# P1-Port-Reader.net
KiCad netlist of a schematic drawn in EAGLE
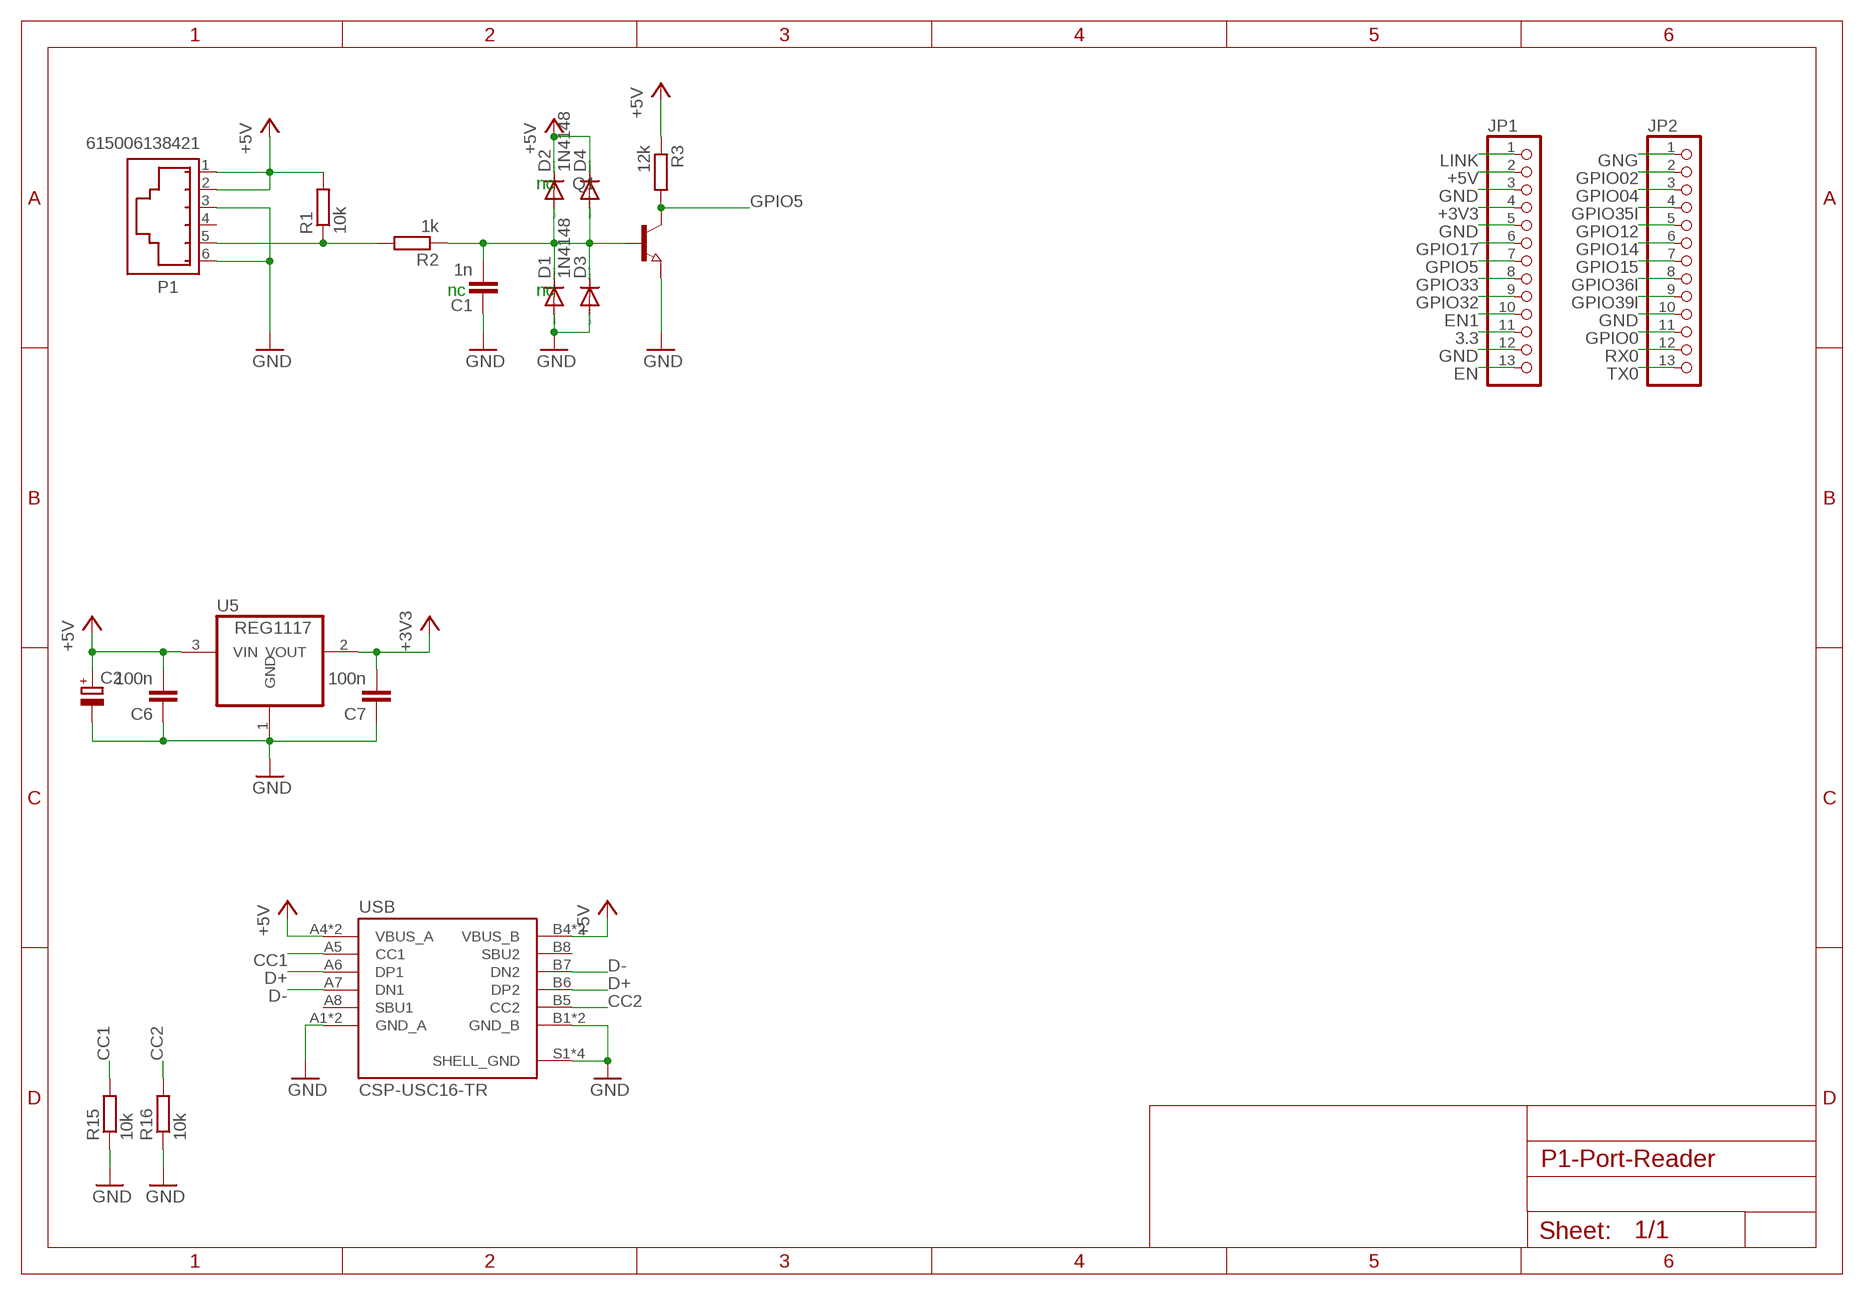
[diagram p0: schematic, sheet 1]

(export (version "E")
  (design (tool "Eeschema 10.0.6"))
  (components
    (comp (ref "C1")
      (value "1n")
      (footprint "eagle-import:C0805")
      (libsource (lib "eagle-import") (part "C-EUC0805"))
    )
    (comp (ref "C2")
      (value "CPOL-EUE5-8.5")
      (footprint "eagle-import:E5-8,5")
      (libsource (lib "eagle-import") (part "CPOL-EUE5-8.5"))
    )
    (comp (ref "C6")
      (value "100n")
      (footprint "eagle-import:C0805")
      (libsource (lib "eagle-import") (part "C-EUC0805"))
    )
    (comp (ref "C7")
      (value "100n")
      (footprint "eagle-import:C0805")
      (libsource (lib "eagle-import") (part "C-EUC0805"))
    )
    (comp (ref "D1")
      (value "1N4148")
      (footprint "eagle-import:SOD123")
      (libsource (lib "eagle-import") (part "DIODE-SOD123"))
    )
    (comp (ref "D2")
      (value "1N4148")
      (footprint "eagle-import:SOD123")
      (libsource (lib "eagle-import") (part "DIODE-SOD123"))
    )
    (comp (ref "D3")
      (value "DIODE-SOD323-W")
      (footprint "eagle-import:SOD323-W")
      (libsource (lib "eagle-import") (part "DIODE-SOD323-W"))
    )
    (comp (ref "D4")
      (value "DIODE-SOD323-W")
      (footprint "eagle-import:SOD323-W")
      (libsource (lib "eagle-import") (part "DIODE-SOD323-W"))
    )
    (comp (ref "JP1")
      (value "PINHD-1X13")
      (footprint "eagle-import:1X13")
      (libsource (lib "eagle-import") (part "PINHD-1X13"))
    )
    (comp (ref "JP2")
      (value "PINHD-1X13")
      (footprint "eagle-import:1X13")
      (libsource (lib "eagle-import") (part "PINHD-1X13"))
    )
    (comp (ref "P1")
      (value "615006138421")
      (footprint "eagle-import:615006138421")
      (libsource (lib "eagle-import") (part "615006138421"))
    )
    (comp (ref "Q1")
      (value "NPN-TRANSISTOR_SOT23")
      (footprint "eagle-import:SOT23")
      (libsource (lib "eagle-import") (part "NPN-TRANSISTOR_SOT23"))
    )
    (comp (ref "R1")
      (value "10k")
      (footprint "eagle-import:R0805")
      (libsource (lib "eagle-import") (part "R-EU_R0805"))
    )
    (comp (ref "R2")
      (value "1k")
      (footprint "eagle-import:R0805")
      (libsource (lib "eagle-import") (part "R-EU_R0805"))
    )
    (comp (ref "R3")
      (value "12k")
      (footprint "eagle-import:R0805")
      (libsource (lib "eagle-import") (part "R-EU_R0805"))
    )
    (comp (ref "R15")
      (value "10k")
      (footprint "eagle-import:R0603")
      (libsource (lib "eagle-import") (part "R-EU_R0603"))
    )
    (comp (ref "R16")
      (value "10k")
      (footprint "eagle-import:R0603")
      (libsource (lib "eagle-import") (part "R-EU_R0603"))
    )
    (comp (ref "U5")
      (value "REG1117")
      (footprint "eagle-import:SOT223")
      (libsource (lib "eagle-import") (part "REG1117"))
    )
    (comp (ref "USB")
      (value "CSP-USC16-TR")
      (footprint "eagle-import:VALCON_CSP-USC16-TR")
      (fields (field (name "MF") "Valcon"))
      (libsource (lib "eagle-import") (part "CSP-USC16-TR"))
    )
  )
  (nets
    (net (code "1") (name "+3V3") (class "Default")
      (node (ref "C7") (pin "2") (pinfunction "2_2") (pintype "passive"))
      (node (ref "JP1") (pin "4") (pinfunction "4_4") (pintype "passive"))
      (node (ref "U5") (pin "2") (pinfunction "VOUT_2") (pintype "output"))
    )
    (net (code "2") (name "+5V") (class "Default")
      (node (ref "C2") (pin "+") (pinfunction "+_+") (pintype "passive"))
      (node (ref "C6") (pin "2") (pinfunction "2_2") (pintype "passive"))
      (node (ref "D2") (pin "C") (pinfunction "C_C") (pintype "passive"))
      (node (ref "D4") (pin "C") (pinfunction "C_C") (pintype "passive"))
      (node (ref "JP1") (pin "2") (pinfunction "2_2") (pintype "passive"))
      (node (ref "P1") (pin "1") (pinfunction "1_1") (pintype "passive"))
      (node (ref "P1") (pin "2") (pinfunction "2_2") (pintype "passive"))
      (node (ref "R1") (pin "2") (pinfunction "2_2") (pintype "passive"))
      (node (ref "R3") (pin "1") (pinfunction "1_1") (pintype "passive"))
      (node (ref "U5") (pin "3") (pinfunction "VIN_3") (pintype "input"))
      (node (ref "USB") (pin "A4") (pinfunction "VBUS_A_A4") (pintype "power_in"))
      (node (ref "USB") (pin "A9") (pinfunction "VBUS_A_A9") (pintype "power_in"))
      (node (ref "USB") (pin "B4") (pinfunction "VBUS_B_B4") (pintype "power_in"))
      (node (ref "USB") (pin "B9") (pinfunction "VBUS_B_B9") (pintype "power_in"))
    )
    (net (code "3") (name "/3.3") (class "Default")
      (node (ref "JP1") (pin "11") (pinfunction "11_11") (pintype "passive"))
    )
    (net (code "4") (name "/CC1") (class "Default")
      (node (ref "R15") (pin "2") (pinfunction "2_2") (pintype "passive"))
      (node (ref "USB") (pin "A5") (pinfunction "CC1_A5") (pintype "bidirectional"))
    )
    (net (code "5") (name "/CC2") (class "Default")
      (node (ref "R16") (pin "2") (pinfunction "2_2") (pintype "passive"))
      (node (ref "USB") (pin "B5") (pinfunction "CC2_B5") (pintype "bidirectional"))
    )
    (net (code "6") (name "/D+") (class "Default")
      (node (ref "USB") (pin "A6") (pinfunction "DP1_A6") (pintype "bidirectional"))
      (node (ref "USB") (pin "B6") (pinfunction "DP2_B6") (pintype "bidirectional"))
    )
    (net (code "7") (name "/D-") (class "Default")
      (node (ref "USB") (pin "A7") (pinfunction "DN1_A7") (pintype "bidirectional"))
      (node (ref "USB") (pin "B7") (pinfunction "DN2_B7") (pintype "bidirectional"))
    )
    (net (code "8") (name "/EN") (class "Default")
      (node (ref "JP1") (pin "13") (pinfunction "13_13") (pintype "passive"))
    )
    (net (code "9") (name "/EN1") (class "Default")
      (node (ref "JP1") (pin "10") (pinfunction "10_10") (pintype "passive"))
    )
    (net (code "10") (name "/GNG") (class "Default")
      (node (ref "JP2") (pin "1") (pinfunction "1_1") (pintype "passive"))
    )
    (net (code "11") (name "/GPIO0") (class "Default")
      (node (ref "JP2") (pin "11") (pinfunction "11_11") (pintype "passive"))
    )
    (net (code "12") (name "/GPIO02") (class "Default")
      (node (ref "JP2") (pin "2") (pinfunction "2_2") (pintype "passive"))
    )
    (net (code "13") (name "/GPIO04") (class "Default")
      (node (ref "JP2") (pin "3") (pinfunction "3_3") (pintype "passive"))
    )
    (net (code "14") (name "/GPIO5") (class "Default")
      (node (ref "JP1") (pin "7") (pinfunction "7_7") (pintype "passive"))
      (node (ref "Q1") (pin "3") (pinfunction "C_3") (pintype "passive"))
      (node (ref "R3") (pin "2") (pinfunction "2_2") (pintype "passive"))
    )
    (net (code "15") (name "/GPIO12") (class "Default")
      (node (ref "JP2") (pin "5") (pinfunction "5_5") (pintype "passive"))
    )
    (net (code "16") (name "/GPIO14") (class "Default")
      (node (ref "JP2") (pin "6") (pinfunction "6_6") (pintype "passive"))
    )
    (net (code "17") (name "/GPIO15") (class "Default")
      (node (ref "JP2") (pin "7") (pinfunction "7_7") (pintype "passive"))
    )
    (net (code "18") (name "/GPIO17") (class "Default")
      (node (ref "JP1") (pin "6") (pinfunction "6_6") (pintype "passive"))
    )
    (net (code "19") (name "/GPIO32") (class "Default")
      (node (ref "JP1") (pin "9") (pinfunction "9_9") (pintype "passive"))
    )
    (net (code "20") (name "/GPIO33") (class "Default")
      (node (ref "JP1") (pin "8") (pinfunction "8_8") (pintype "passive"))
    )
    (net (code "21") (name "/GPIO35I") (class "Default")
      (node (ref "JP2") (pin "4") (pinfunction "4_4") (pintype "passive"))
    )
    (net (code "22") (name "/GPIO36I") (class "Default")
      (node (ref "JP2") (pin "8") (pinfunction "8_8") (pintype "passive"))
    )
    (net (code "23") (name "/GPIO39I") (class "Default")
      (node (ref "JP2") (pin "9") (pinfunction "9_9") (pintype "passive"))
    )
    (net (code "24") (name "/LINK") (class "Default")
      (node (ref "JP1") (pin "1") (pinfunction "1_1") (pintype "passive"))
    )
    (net (code "25") (name "/RX0") (class "Default")
      (node (ref "JP2") (pin "12") (pinfunction "12_12") (pintype "passive"))
    )
    (net (code "26") (name "/TX0") (class "Default")
      (node (ref "JP2") (pin "13") (pinfunction "13_13") (pintype "passive"))
    )
    (net (code "27") (name "GND") (class "Default")
      (node (ref "C1") (pin "1") (pinfunction "1_1") (pintype "passive"))
      (node (ref "C2") (pin "-") (pinfunction "-_-") (pintype "passive"))
      (node (ref "C6") (pin "1") (pinfunction "1_1") (pintype "passive"))
      (node (ref "C7") (pin "1") (pinfunction "1_1") (pintype "passive"))
      (node (ref "D1") (pin "A") (pinfunction "A_A") (pintype "passive"))
      (node (ref "D3") (pin "A") (pinfunction "A_A") (pintype "passive"))
      (node (ref "JP1") (pin "12") (pinfunction "12_12") (pintype "passive"))
      (node (ref "JP1") (pin "3") (pinfunction "3_3") (pintype "passive"))
      (node (ref "JP1") (pin "5") (pinfunction "5_5") (pintype "passive"))
      (node (ref "JP2") (pin "10") (pinfunction "10_10") (pintype "passive"))
      (node (ref "P1") (pin "3") (pinfunction "3_3") (pintype "passive"))
      (node (ref "P1") (pin "6") (pinfunction "6_6") (pintype "passive"))
      (node (ref "Q1") (pin "2") (pinfunction "E_2") (pintype "passive"))
      (node (ref "R15") (pin "1") (pinfunction "1_1") (pintype "passive"))
      (node (ref "R16") (pin "1") (pinfunction "1_1") (pintype "passive"))
      (node (ref "U5") (pin "1") (pinfunction "GND_1") (pintype "power_in"))
      (node (ref "USB") (pin "A1") (pinfunction "GND_A_A1") (pintype "power_in"))
      (node (ref "USB") (pin "A12") (pinfunction "GND_A_A12") (pintype "power_in"))
      (node (ref "USB") (pin "B1") (pinfunction "GND_B_B1") (pintype "power_in"))
      (node (ref "USB") (pin "B12") (pinfunction "GND_B_B12") (pintype "power_in"))
      (node (ref "USB") (pin "S1") (pinfunction "SHELL_GND_S1") (pintype "power_in"))
      (node (ref "USB") (pin "S2") (pinfunction "SHELL_GND_S2") (pintype "power_in"))
      (node (ref "USB") (pin "S3") (pinfunction "SHELL_GND_S3") (pintype "power_in"))
      (node (ref "USB") (pin "S4") (pinfunction "SHELL_GND_S4") (pintype "power_in"))
    )
    (net (code "28") (name "Net-(P1-Pad5)") (class "Default")
      (node (ref "P1") (pin "5") (pinfunction "5_5") (pintype "passive"))
      (node (ref "R1") (pin "1") (pinfunction "1_1") (pintype "passive"))
      (node (ref "R2") (pin "2") (pinfunction "2_2") (pintype "passive"))
    )
    (net (code "29") (name "Net-(Q1-B)") (class "Default")
      (node (ref "C1") (pin "2") (pinfunction "2_2") (pintype "passive"))
      (node (ref "D1") (pin "C") (pinfunction "C_C") (pintype "passive"))
      (node (ref "D2") (pin "A") (pinfunction "A_A") (pintype "passive"))
      (node (ref "D3") (pin "C") (pinfunction "C_C") (pintype "passive"))
      (node (ref "D4") (pin "A") (pinfunction "A_A") (pintype "passive"))
      (node (ref "Q1") (pin "1") (pinfunction "B_1") (pintype "passive"))
      (node (ref "R2") (pin "1") (pinfunction "1_1") (pintype "passive"))
    )
    (net (code "30") (name "unconnected-(P1-Pad4)") (class "Default")
      (node (ref "P1") (pin "4") (pinfunction "4_4") (pintype "passive"))
    )
    (net (code "31") (name "unconnected-(USB-SBU1-PadA8)") (class "Default")
      (node (ref "USB") (pin "A8") (pinfunction "SBU1_A8") (pintype "bidirectional"))
    )
    (net (code "32") (name "unconnected-(USB-SBU2-PadB8)") (class "Default")
      (node (ref "USB") (pin "B8") (pinfunction "SBU2_B8") (pintype "bidirectional"))
    )
  )
)
